# CUSTOMIZED_UN0O_BOARD.net
KiCad netlist of a schematic drawn in EAGLE
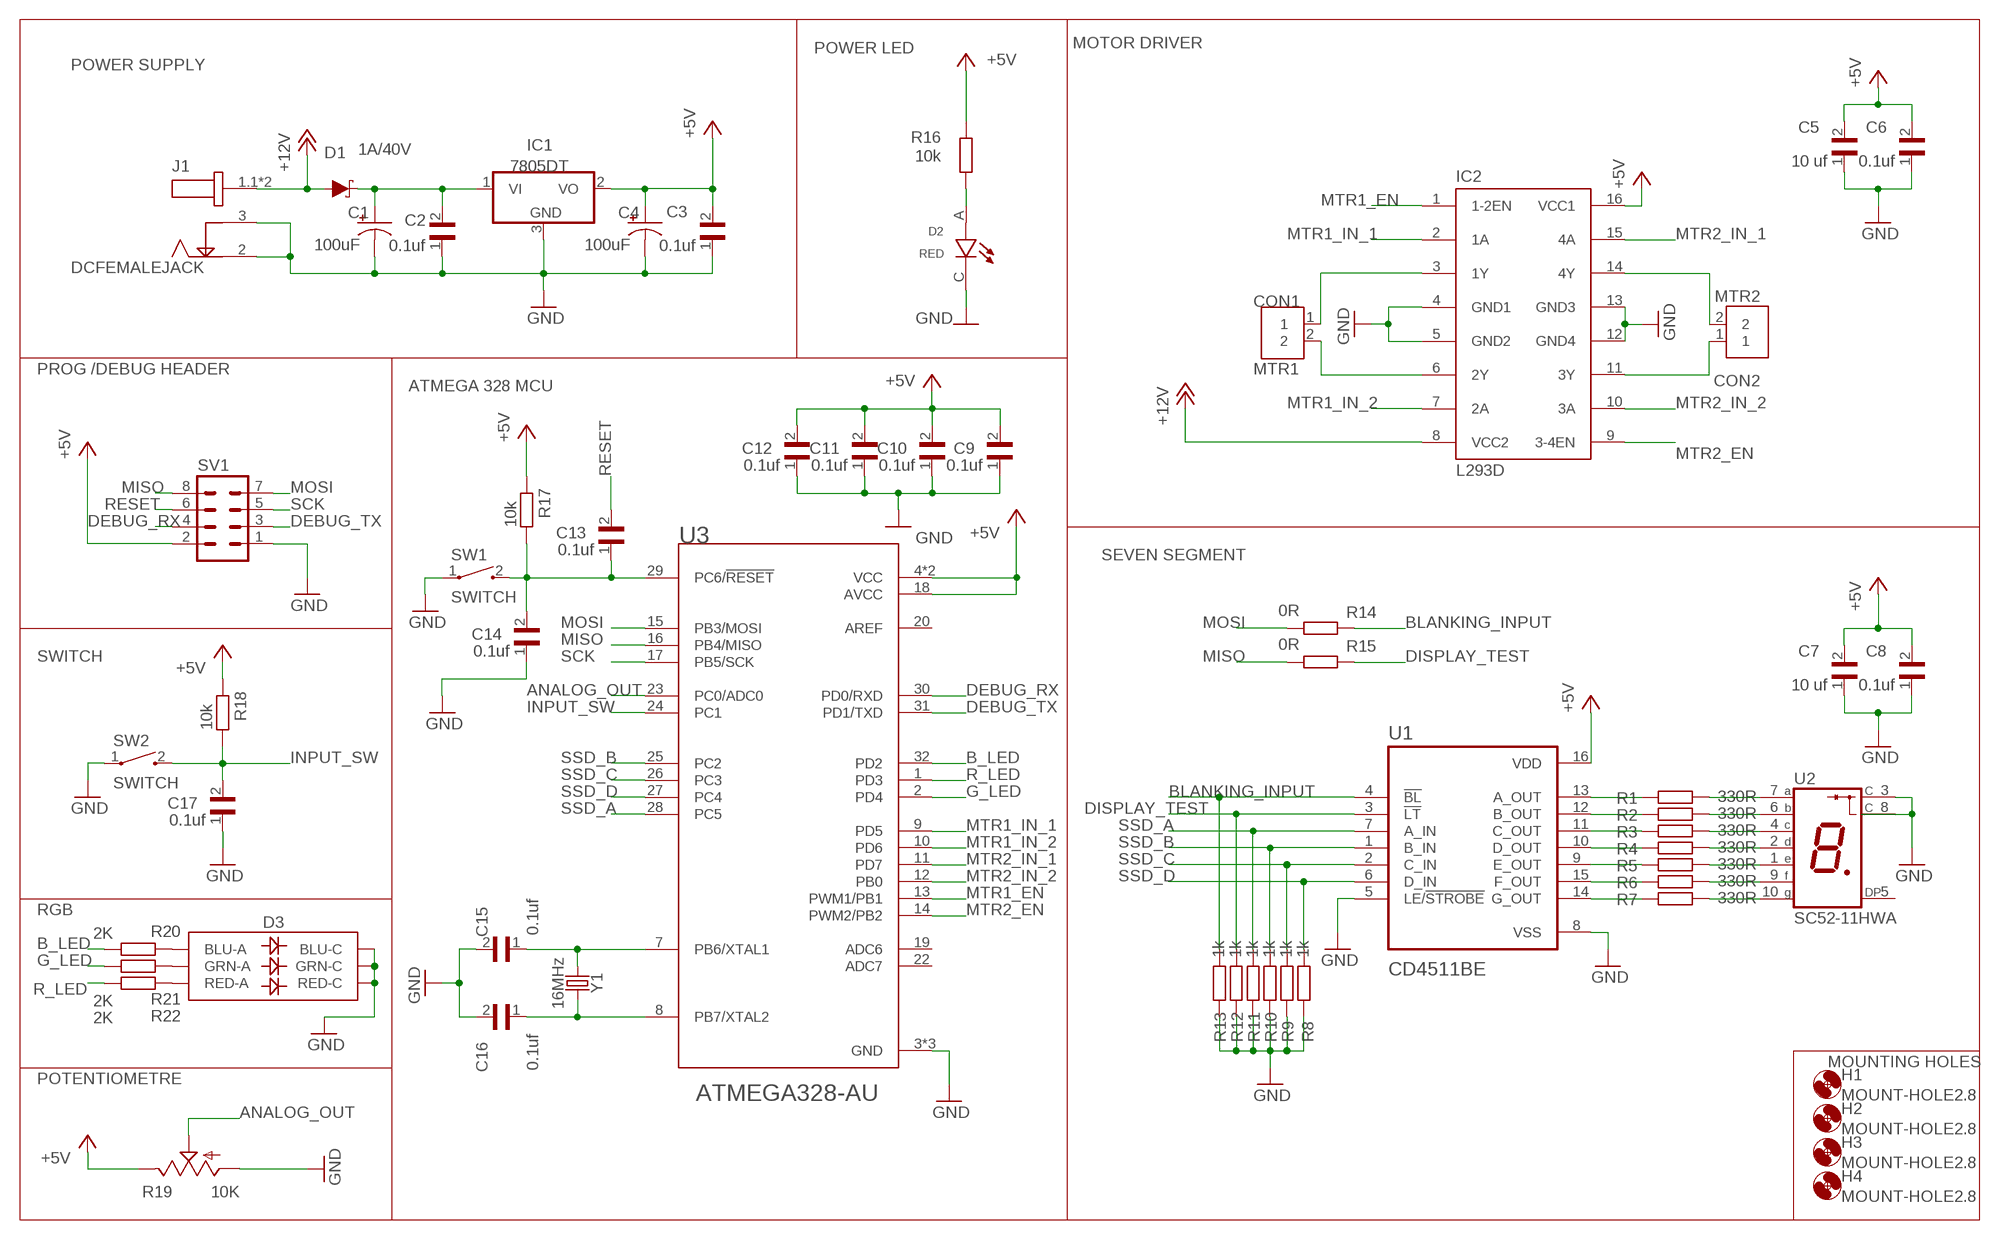
[diagram p0: schematic, sheet 1]

(export (version "E")
  (design (tool "Eeschema 10.0.6"))
  (components
    (comp (ref "C1")
      (value "100uF")
      (footprint "eagle-import:CPOL-RADIAL-2.5MM-6.5MM")
      (libsource (lib "eagle-import") (part "100UF-POLAR-RADIAL-2.5MM-25V-20%"))
    )
    (comp (ref "C2")
      (value "CAPACITOR")
      (footprint "eagle-import:C0603")
      (fields
        (field (name "MF") "TDK")
        (field (name "MP") "CGA3E2X7R1H104K080AA")
        (field (name "C2") "0.1uf")
        (field (name "NULL") "0.1uf")
      )
      (libsource (lib "eagle-import") (part "CAPACITOR"))
    )
    (comp (ref "C3")
      (value "CAPACITOR")
      (footprint "eagle-import:C0603")
      (fields
        (field (name "MF") "TDK")
        (field (name "MP") "CGA3E2X7R1H104K080AA")
        (field (name "NULL") "0.1uf")
      )
      (libsource (lib "eagle-import") (part "CAPACITOR"))
    )
    (comp (ref "C4")
      (value "100uF")
      (footprint "eagle-import:CPOL-RADIAL-2.5MM-6.5MM")
      (libsource (lib "eagle-import") (part "100UF-POLAR-RADIAL-2.5MM-25V-20%"))
    )
    (comp (ref "C5")
      (value "CAPACITOR")
      (footprint "eagle-import:C0603")
      (fields
        (field (name "MF") "TDK")
        (field (name "MP") "CGA3E2X7R1H104K080AA")
        (field (name "C3") "10 uf")
        (field (name "NO") "10")
        (field (name "NULL") "0.1uf")
      )
      (libsource (lib "eagle-import") (part "CAPACITOR"))
    )
    (comp (ref "C6")
      (value "CAPACITOR")
      (footprint "eagle-import:C0603")
      (fields
        (field (name "MF") "TDK")
        (field (name "MP") "CGA3E2X7R1H104K080AA")
        (field (name "NULL") "0.1uf")
      )
      (libsource (lib "eagle-import") (part "CAPACITOR"))
    )
    (comp (ref "C7")
      (value "CAPACITOR")
      (footprint "eagle-import:C0603")
      (fields
        (field (name "MF") "TDK")
        (field (name "MP") "CGA3E2X7R1H104K080AA")
        (field (name "C3") "10 uf")
        (field (name "NO") "10")
        (field (name "NULL") "0.1uf")
      )
      (libsource (lib "eagle-import") (part "CAPACITOR"))
    )
    (comp (ref "C8")
      (value "CAPACITOR")
      (footprint "eagle-import:C0603")
      (fields
        (field (name "MF") "TDK")
        (field (name "MP") "CGA3E2X7R1H104K080AA")
        (field (name "NULL") "0.1uf")
      )
      (libsource (lib "eagle-import") (part "CAPACITOR"))
    )
    (comp (ref "C9")
      (value "CAPACITOR")
      (footprint "eagle-import:C0603")
      (fields
        (field (name "MF") "TDK")
        (field (name "MP") "CGA3E2X7R1H104K080AA")
        (field (name "NULL") "0.1uf")
      )
      (libsource (lib "eagle-import") (part "CAPACITOR"))
    )
    (comp (ref "C10")
      (value "CAPACITOR")
      (footprint "eagle-import:C0603")
      (fields
        (field (name "MF") "TDK")
        (field (name "MP") "CGA3E2X7R1H104K080AA")
        (field (name "NULL") "0.1uf")
      )
      (libsource (lib "eagle-import") (part "CAPACITOR"))
    )
    (comp (ref "C11")
      (value "CAPACITOR")
      (footprint "eagle-import:C0603")
      (fields
        (field (name "MF") "TDK")
        (field (name "MP") "CGA3E2X7R1H104K080AA")
        (field (name "NULL") "0.1uf")
      )
      (libsource (lib "eagle-import") (part "CAPACITOR"))
    )
    (comp (ref "C12")
      (value "CAPACITOR")
      (footprint "eagle-import:C0603")
      (fields
        (field (name "MF") "TDK")
        (field (name "MP") "CGA3E2X7R1H104K080AA")
        (field (name "NULL") "0.1uf")
      )
      (libsource (lib "eagle-import") (part "CAPACITOR"))
    )
    (comp (ref "C13")
      (value "CAPACITOR")
      (footprint "eagle-import:C0603")
      (fields
        (field (name "MF") "TDK")
        (field (name "MP") "CGA3E2X7R1H104K080AA")
        (field (name "NULL") "0.1uf")
      )
      (libsource (lib "eagle-import") (part "CAPACITOR"))
    )
    (comp (ref "C14")
      (value "CAPACITOR")
      (footprint "eagle-import:C0603")
      (fields
        (field (name "MF") "TDK")
        (field (name "MP") "CGA3E2X7R1H104K080AA")
        (field (name "NULL") "0.1uf")
      )
      (libsource (lib "eagle-import") (part "CAPACITOR"))
    )
    (comp (ref "C15")
      (value "CAPACITOR")
      (footprint "eagle-import:C0603")
      (fields
        (field (name "MF") "TDK")
        (field (name "MP") "CGA3E2X7R1H104K080AA")
        (field (name "NULL") "0.1uf")
      )
      (libsource (lib "eagle-import") (part "CAPACITOR"))
    )
    (comp (ref "C16")
      (value "22pf")
      (footprint "eagle-import:C0603")
      (fields
        (field (name "MF") "TDK")
        (field (name "MP") "CGA3E2X7R1H104K080AA")
        (field (name "NULL") "0.1uf")
      )
      (libsource (lib "eagle-import") (part "CAPACITOR"))
    )
    (comp (ref "C17")
      (value "CAPACITOR")
      (footprint "eagle-import:C0603")
      (fields
        (field (name "MF") "TDK")
        (field (name "MP") "CGA3E2X7R1H104K080AA")
        (field (name "NULL") "0.1uf")
      )
      (libsource (lib "eagle-import") (part "CAPACITOR"))
    )
    (comp (ref "D1")
      (value "3A/40V/500mV")
      (footprint "eagle-import:SMA-DIODE")
      (fields (field (name "D1") "1A,40V") (field (name "NULL") "1A/40V"))
      (libsource (lib "eagle-import") (part "DIODE-SCHOTTKY-B340A"))
    )
    (comp (ref "D2")
      (value "RED")
      (footprint "eagle-import:LEDC1608X65N")
      (fields (field (name "MF") "Lite-On") (field (name "MP") "LTW-C191TLA"))
      (libsource (lib "eagle-import") (part "LTW-C191TLA"))
    )
    (comp (ref "D3")
      (value "LED-RGBNO_IC")
      (footprint "eagle-import:LED-TRICOLOR-5050")
      (libsource (lib "eagle-import") (part "LED-RGBNO_IC"))
    )
    (comp (ref "H1")
      (value "MOUNT-HOLE2.8")
      (footprint "eagle-import:2,8")
      (libsource (lib "eagle-import") (part "MOUNT-HOLE2.8"))
    )
    (comp (ref "H2")
      (value "MOUNT-HOLE2.8")
      (footprint "eagle-import:2,8")
      (libsource (lib "eagle-import") (part "MOUNT-HOLE2.8"))
    )
    (comp (ref "H3")
      (value "MOUNT-HOLE2.8")
      (footprint "eagle-import:2,8")
      (libsource (lib "eagle-import") (part "MOUNT-HOLE2.8"))
    )
    (comp (ref "H4")
      (value "MOUNT-HOLE2.8")
      (footprint "eagle-import:2,8")
      (libsource (lib "eagle-import") (part "MOUNT-HOLE2.8"))
    )
    (comp (ref "IC1")
      (value "7806DT")
      (footprint "eagle-import:TO252")
      (fields (field (name "K") "7805DT"))
      (libsource (lib "eagle-import") (part "78DT06"))
    )
    (comp (ref "IC2")
      (value "L293D")
      (footprint "eagle-import:DIL16")
      (libsource (lib "eagle-import") (part "L293D"))
    )
    (comp (ref "J1")
      (value "DCJ200-05-A-XX-X_REVA")
      (footprint "eagle-import:GCT_DCJ200-05-A-XX-X_REVA")
      (fields (field (name "MF") "Global Connector Technology") (field (name "MP") "DCJ200-05-A-K1-A"))
      (libsource (lib "eagle-import") (part "DCJ200-05-A-XX-X_REVA"))
    )
    (comp (ref "J2")
      (value "282836-2")
      (footprint "eagle-import:CONN_282836-2")
      (fields (field (name "MF") "TE Connectivity"))
      (libsource (lib "eagle-import") (part "282836-2"))
    )
    (comp (ref "J3")
      (value "282836-2")
      (footprint "eagle-import:CONN_282836-2")
      (fields (field (name "MF") "TE Connectivity"))
      (libsource (lib "eagle-import") (part "282836-2"))
    )
    (comp (ref "R1")
      (value "330R")
      (footprint "eagle-import:R0603")
      (fields (field (name "MF") "Yageo"))
      (libsource (lib "eagle-import") (part "RESISTOR"))
    )
    (comp (ref "R2")
      (value "330R")
      (footprint "eagle-import:R0603")
      (fields (field (name "MF") "Yageo"))
      (libsource (lib "eagle-import") (part "RESISTOR"))
    )
    (comp (ref "R3")
      (value "330R")
      (footprint "eagle-import:R0603")
      (fields (field (name "MF") "Yageo"))
      (libsource (lib "eagle-import") (part "RESISTOR"))
    )
    (comp (ref "R4")
      (value "330R")
      (footprint "eagle-import:R0603")
      (fields (field (name "MF") "Yageo"))
      (libsource (lib "eagle-import") (part "RESISTOR"))
    )
    (comp (ref "R5")
      (value "330R")
      (footprint "eagle-import:R0603")
      (fields (field (name "MF") "Yageo"))
      (libsource (lib "eagle-import") (part "RESISTOR"))
    )
    (comp (ref "R6")
      (value "330R")
      (footprint "eagle-import:R0603")
      (fields (field (name "MF") "Yageo"))
      (libsource (lib "eagle-import") (part "RESISTOR"))
    )
    (comp (ref "R7")
      (value "330R")
      (footprint "eagle-import:R0603")
      (fields (field (name "MF") "Yageo"))
      (libsource (lib "eagle-import") (part "RESISTOR"))
    )
    (comp (ref "R8")
      (value "1k")
      (footprint "eagle-import:R0603")
      (fields (field (name "MF") "Yageo"))
      (libsource (lib "eagle-import") (part "RESISTOR"))
    )
    (comp (ref "R9")
      (value "1k")
      (footprint "eagle-import:R0603")
      (fields (field (name "MF") "Yageo"))
      (libsource (lib "eagle-import") (part "RESISTOR"))
    )
    (comp (ref "R10")
      (value "1k")
      (footprint "eagle-import:R0603")
      (fields (field (name "MF") "Yageo"))
      (libsource (lib "eagle-import") (part "RESISTOR"))
    )
    (comp (ref "R11")
      (value "1k")
      (footprint "eagle-import:R0603")
      (fields (field (name "MF") "Yageo"))
      (libsource (lib "eagle-import") (part "RESISTOR"))
    )
    (comp (ref "R12")
      (value "1k")
      (footprint "eagle-import:R0603")
      (fields (field (name "MF") "Yageo"))
      (libsource (lib "eagle-import") (part "RESISTOR"))
    )
    (comp (ref "R13")
      (value "1k")
      (footprint "eagle-import:R0603")
      (fields (field (name "MF") "Yageo"))
      (libsource (lib "eagle-import") (part "RESISTOR"))
    )
    (comp (ref "R14")
      (value "0R")
      (footprint "eagle-import:R0603")
      (fields (field (name "MF") "Yageo"))
      (libsource (lib "eagle-import") (part "RESISTOR"))
    )
    (comp (ref "R15")
      (value "0R")
      (footprint "eagle-import:R0603")
      (fields (field (name "MF") "Yageo"))
      (libsource (lib "eagle-import") (part "RESISTOR"))
    )
    (comp (ref "R16")
      (value "10k")
      (footprint "eagle-import:R0603")
      (fields (field (name "MF") "Yageo"))
      (libsource (lib "eagle-import") (part "RESISTOR"))
    )
    (comp (ref "R17")
      (value "10k")
      (footprint "eagle-import:R0603")
      (fields (field (name "MF") "Yageo"))
      (libsource (lib "eagle-import") (part "RESISTOR"))
    )
    (comp (ref "R18")
      (value "10k")
      (footprint "eagle-import:R0603")
      (fields (field (name "MF") "Yageo"))
      (libsource (lib "eagle-import") (part "RESISTOR"))
    )
    (comp (ref "R19")
      (value "10K")
      (footprint "eagle-import:S64W")
      (libsource (lib "eagle-import") (part "TRIM_US-S64W"))
    )
    (comp (ref "R20")
      (value "2K")
      (footprint "eagle-import:R0603")
      (fields (field (name "MF") "Yageo"))
      (libsource (lib "eagle-import") (part "RESISTOR"))
    )
    (comp (ref "R21")
      (value "2K")
      (footprint "eagle-import:R0603")
      (fields (field (name "MF") "Yageo"))
      (libsource (lib "eagle-import") (part "RESISTOR"))
    )
    (comp (ref "R22")
      (value "2K")
      (footprint "eagle-import:R0603")
      (fields (field (name "MF") "Yageo"))
      (libsource (lib "eagle-import") (part "RESISTOR"))
    )
    (comp (ref "SV1")
      (value "MA04-2")
      (footprint "eagle-import:MA04-2")
      (libsource (lib "eagle-import") (part "MA04-2"))
    )
    (comp (ref "SW1")
      (value "SWITCH")
      (footprint "eagle-import:SW_1437566-3")
      (fields (field (name "COMMENT") "1437566-3") (field (name "MF") "TE Connectivity"))
      (libsource (lib "eagle-import") (part "1437566-3"))
    )
    (comp (ref "SW2")
      (value "SWITCH")
      (footprint "eagle-import:SW_1437566-3")
      (fields (field (name "COMMENT") "1437566-3") (field (name "MF") "TE Connectivity"))
      (libsource (lib "eagle-import") (part "1437566-3"))
    )
    (comp (ref "U1")
      (value "CD4511BE")
      (footprint "eagle-import:DIP794W45P254L1969H508Q16")
      (fields (field (name "MF") "Texas Instruments"))
      (libsource (lib "eagle-import") (part "CD4511BE"))
    )
    (comp (ref "U2")
      (value "SC52-11HWA")
      (footprint "eagle-import:LED_SC52-11HWA")
      (fields (field (name "MF") "Kingbright"))
      (libsource (lib "eagle-import") (part "SC52-11HWA"))
    )
    (comp (ref "U3")
      (value "ATMEGA328-AU")
      (footprint "eagle-import:QFP80P900X900X120-32N")
      (fields (field (name "MF") "Microchip"))
      (libsource (lib "eagle-import") (part "ATMEGA328-AU"))
    )
    (comp (ref "Y1")
      (value "16MHz")
      (footprint "eagle-import:HC49US")
      (libsource (lib "eagle-import") (part "CRYSTAL-16MHZPTH-HC49US"))
    )
  )
  (nets
    (net (code "1") (name "+5V") (class "Default")
      (node (ref "C10") (pin "2") (pinfunction "2_2") (pintype "passive"))
      (node (ref "C11") (pin "2") (pinfunction "2_2") (pintype "passive"))
      (node (ref "C12") (pin "2") (pinfunction "2_2") (pintype "passive"))
      (node (ref "C3") (pin "2") (pinfunction "2_2") (pintype "passive"))
      (node (ref "C4") (pin "1") (pinfunction "+_1") (pintype "passive"))
      (node (ref "C5") (pin "2") (pinfunction "2_2") (pintype "passive"))
      (node (ref "C6") (pin "2") (pinfunction "2_2") (pintype "passive"))
      (node (ref "C7") (pin "2") (pinfunction "2_2") (pintype "passive"))
      (node (ref "C8") (pin "2") (pinfunction "2_2") (pintype "passive"))
      (node (ref "C9") (pin "2") (pinfunction "2_2") (pintype "passive"))
      (node (ref "IC1") (pin "2") (pinfunction "VO_2") (pintype "passive"))
      (node (ref "IC2") (pin "16") (pinfunction "VCC1_16") (pintype "power_in"))
      (node (ref "R16") (pin "2") (pinfunction "2_2") (pintype "passive"))
      (node (ref "R17") (pin "2") (pinfunction "2_2") (pintype "passive"))
      (node (ref "R18") (pin "2") (pinfunction "2_2") (pintype "passive"))
      (node (ref "R19") (pin "E") (pinfunction "E_E") (pintype "passive"))
      (node (ref "SV1") (pin "2") (pinfunction "2_2") (pintype "passive"))
      (node (ref "U1") (pin "16") (pinfunction "VDD_16") (pintype "power_in"))
      (node (ref "U3") (pin "18") (pinfunction "AVCC_18") (pintype "power_in"))
      (node (ref "U3") (pin "4") (pinfunction "VCC_4") (pintype "power_in"))
      (node (ref "U3") (pin "6") (pinfunction "VCC_6") (pintype "power_in"))
    )
    (net (code "2") (name "+12V") (class "Default")
      (node (ref "D1") (pin "A") (pinfunction "A_A") (pintype "passive"))
      (node (ref "IC2") (pin "8") (pinfunction "VCC2_8") (pintype "power_in"))
      (node (ref "J1") (pin "1.1") (pinfunction "1_1.1") (pintype "passive"))
      (node (ref "J1") (pin "1.2") (pinfunction "1_1.2") (pintype "passive"))
    )
    (net (code "3") (name "ANALOG_OUT") (class "Default")
      (node (ref "R19") (pin "S") (pinfunction "S_S") (pintype "passive"))
      (node (ref "U3") (pin "23") (pinfunction "PC0/ADC0_23") (pintype "bidirectional"))
    )
    (net (code "4") (name "BLANKING_INPUT") (class "Default")
      (node (ref "R13") (pin "2") (pinfunction "2_2") (pintype "passive"))
      (node (ref "R14") (pin "2") (pinfunction "2_2") (pintype "passive"))
      (node (ref "U1") (pin "4") (pinfunction "~{BL}_4") (pintype "input"))
    )
    (net (code "5") (name "B_LED") (class "Default")
      (node (ref "R20") (pin "2") (pinfunction "2_2") (pintype "passive"))
      (node (ref "U3") (pin "32") (pinfunction "PD2_32") (pintype "bidirectional"))
    )
    (net (code "6") (name "DEBUG_RX") (class "Default")
      (node (ref "SV1") (pin "4") (pinfunction "4_4") (pintype "passive"))
      (node (ref "U3") (pin "30") (pinfunction "PD0/RXD_30") (pintype "bidirectional"))
    )
    (net (code "7") (name "DEBUG_TX") (class "Default")
      (node (ref "SV1") (pin "3") (pinfunction "3_3") (pintype "passive"))
      (node (ref "U3") (pin "31") (pinfunction "PD1/TXD_31") (pintype "bidirectional"))
    )
    (net (code "8") (name "DISPLAY_TEST") (class "Default")
      (node (ref "R12") (pin "2") (pinfunction "2_2") (pintype "passive"))
      (node (ref "R15") (pin "2") (pinfunction "2_2") (pintype "passive"))
      (node (ref "U1") (pin "3") (pinfunction "~{LT}_3") (pintype "input"))
    )
    (net (code "9") (name "GND") (class "Default")
      (node (ref "C1") (pin "2") (pinfunction "-_2") (pintype "passive"))
      (node (ref "C10") (pin "1") (pinfunction "1_1") (pintype "passive"))
      (node (ref "C11") (pin "1") (pinfunction "1_1") (pintype "passive"))
      (node (ref "C12") (pin "1") (pinfunction "1_1") (pintype "passive"))
      (node (ref "C14") (pin "1") (pinfunction "1_1") (pintype "passive"))
      (node (ref "C15") (pin "2") (pinfunction "2_2") (pintype "passive"))
      (node (ref "C16") (pin "2") (pinfunction "2_2") (pintype "passive"))
      (node (ref "C17") (pin "1") (pinfunction "1_1") (pintype "passive"))
      (node (ref "C2") (pin "1") (pinfunction "1_1") (pintype "passive"))
      (node (ref "C3") (pin "1") (pinfunction "1_1") (pintype "passive"))
      (node (ref "C4") (pin "2") (pinfunction "-_2") (pintype "passive"))
      (node (ref "C5") (pin "1") (pinfunction "1_1") (pintype "passive"))
      (node (ref "C6") (pin "1") (pinfunction "1_1") (pintype "passive"))
      (node (ref "C7") (pin "1") (pinfunction "1_1") (pintype "passive"))
      (node (ref "C8") (pin "1") (pinfunction "1_1") (pintype "passive"))
      (node (ref "C9") (pin "1") (pinfunction "1_1") (pintype "passive"))
      (node (ref "D2") (pin "C") (pinfunction "C_C") (pintype "passive"))
      (node (ref "D3") (pin "4") (pinfunction "BLU-C_4") (pintype "bidirectional"))
      (node (ref "D3") (pin "5") (pinfunction "RED-C_5") (pintype "bidirectional"))
      (node (ref "D3") (pin "6") (pinfunction "GRN-C_6") (pintype "bidirectional"))
      (node (ref "IC1") (pin "3") (pinfunction "GND_3") (pintype "passive"))
      (node (ref "IC2") (pin "12") (pinfunction "GND4_12") (pintype "power_in"))
      (node (ref "IC2") (pin "13") (pinfunction "GND3_13") (pintype "power_in"))
      (node (ref "IC2") (pin "4") (pinfunction "GND1_4") (pintype "power_in"))
      (node (ref "IC2") (pin "5") (pinfunction "GND2_5") (pintype "power_in"))
      (node (ref "J1") (pin "2") (pinfunction "2_2") (pintype "passive"))
      (node (ref "J1") (pin "3") (pinfunction "3_3") (pintype "passive"))
      (node (ref "R10") (pin "1") (pinfunction "1_1") (pintype "passive"))
      (node (ref "R11") (pin "1") (pinfunction "1_1") (pintype "passive"))
      (node (ref "R12") (pin "1") (pinfunction "1_1") (pintype "passive"))
      (node (ref "R13") (pin "1") (pinfunction "1_1") (pintype "passive"))
      (node (ref "R19") (pin "A") (pinfunction "A_A") (pintype "passive"))
      (node (ref "R8") (pin "1") (pinfunction "1_1") (pintype "passive"))
      (node (ref "R9") (pin "1") (pinfunction "1_1") (pintype "passive"))
      (node (ref "SV1") (pin "1") (pinfunction "1_1") (pintype "passive"))
      (node (ref "SW1") (pin "1") (pinfunction "1_1") (pintype "passive"))
      (node (ref "SW2") (pin "1") (pinfunction "1_1") (pintype "passive"))
      (node (ref "U1") (pin "5") (pinfunction "LE/~{STROBE}_5") (pintype "input"))
      (node (ref "U1") (pin "8") (pinfunction "VSS_8") (pintype "power_in"))
      (node (ref "U2") (pin "3") (pinfunction "C_3") (pintype "passive"))
      (node (ref "U2") (pin "8") (pinfunction "C_8") (pintype "passive"))
      (node (ref "U3") (pin "21") (pinfunction "GND_21") (pintype "power_in"))
      (node (ref "U3") (pin "3") (pinfunction "GND_3") (pintype "power_in"))
      (node (ref "U3") (pin "5") (pinfunction "GND_5") (pintype "power_in"))
    )
    (net (code "10") (name "G_LED") (class "Default")
      (node (ref "R21") (pin "2") (pinfunction "2_2") (pintype "passive"))
      (node (ref "U3") (pin "2") (pinfunction "PD4_2") (pintype "bidirectional"))
    )
    (net (code "11") (name "INPUT_SW") (class "Default")
      (node (ref "C17") (pin "2") (pinfunction "2_2") (pintype "passive"))
      (node (ref "R18") (pin "1") (pinfunction "1_1") (pintype "passive"))
      (node (ref "SW2") (pin "2") (pinfunction "2_2") (pintype "passive"))
      (node (ref "U3") (pin "24") (pinfunction "PC1_24") (pintype "bidirectional"))
    )
    (net (code "12") (name "MISO") (class "Default")
      (node (ref "R15") (pin "1") (pinfunction "1_1") (pintype "passive"))
      (node (ref "SV1") (pin "8") (pinfunction "8_8") (pintype "passive"))
      (node (ref "U3") (pin "16") (pinfunction "PB4/MISO_16") (pintype "bidirectional"))
    )
    (net (code "13") (name "MOSI") (class "Default")
      (node (ref "R14") (pin "1") (pinfunction "1_1") (pintype "passive"))
      (node (ref "SV1") (pin "7") (pinfunction "7_7") (pintype "passive"))
      (node (ref "U3") (pin "15") (pinfunction "PB3/MOSI_15") (pintype "bidirectional"))
    )
    (net (code "14") (name "MTR1_EN") (class "Default")
      (node (ref "IC2") (pin "1") (pinfunction "1-2EN_1") (pintype "input"))
      (node (ref "U3") (pin "13") (pinfunction "PWM1/PB1_13") (pintype "bidirectional"))
    )
    (net (code "15") (name "MTR1_IN_1") (class "Default")
      (node (ref "IC2") (pin "2") (pinfunction "1A_2") (pintype "input"))
      (node (ref "U3") (pin "9") (pinfunction "PD5_9") (pintype "bidirectional"))
    )
    (net (code "16") (name "MTR1_IN_2") (class "Default")
      (node (ref "IC2") (pin "7") (pinfunction "2A_7") (pintype "input"))
      (node (ref "U3") (pin "10") (pinfunction "PD6_10") (pintype "bidirectional"))
    )
    (net (code "17") (name "MTR2_EN") (class "Default")
      (node (ref "IC2") (pin "9") (pinfunction "3-4EN_9") (pintype "input"))
      (node (ref "U3") (pin "14") (pinfunction "PWM2/PB2_14") (pintype "bidirectional"))
    )
    (net (code "18") (name "MTR2_IN_1") (class "Default")
      (node (ref "IC2") (pin "15") (pinfunction "4A_15") (pintype "input"))
      (node (ref "U3") (pin "11") (pinfunction "PD7_11") (pintype "bidirectional"))
    )
    (net (code "19") (name "MTR2_IN_2") (class "Default")
      (node (ref "IC2") (pin "10") (pinfunction "3A_10") (pintype "input"))
      (node (ref "U3") (pin "12") (pinfunction "PB0_12") (pintype "bidirectional"))
    )
    (net (code "20") (name "Net-(C1-+)") (class "Default")
      (node (ref "C1") (pin "1") (pinfunction "+_1") (pintype "passive"))
      (node (ref "C2") (pin "2") (pinfunction "2_2") (pintype "passive"))
      (node (ref "D1") (pin "C") (pinfunction "C_C") (pintype "passive"))
      (node (ref "IC1") (pin "1") (pinfunction "VI_1") (pintype "input"))
    )
    (net (code "21") (name "Net-(D2-PadA)") (class "Default")
      (node (ref "D2") (pin "A") (pinfunction "A_A") (pintype "passive"))
      (node (ref "R16") (pin "1") (pinfunction "1_1") (pintype "passive"))
    )
    (net (code "22") (name "Net-(D3-BLU-A)") (class "Default")
      (node (ref "D3") (pin "3") (pinfunction "BLU-A_3") (pintype "bidirectional"))
      (node (ref "R20") (pin "1") (pinfunction "1_1") (pintype "passive"))
    )
    (net (code "23") (name "Net-(D3-GRN-A)") (class "Default")
      (node (ref "D3") (pin "1") (pinfunction "GRN-A_1") (pintype "bidirectional"))
      (node (ref "R21") (pin "1") (pinfunction "1_1") (pintype "passive"))
    )
    (net (code "24") (name "Net-(D3-RED-A)") (class "Default")
      (node (ref "D3") (pin "2") (pinfunction "RED-A_2") (pintype "bidirectional"))
      (node (ref "R22") (pin "1") (pinfunction "1_1") (pintype "passive"))
    )
    (net (code "25") (name "Net-(IC2-1Y)") (class "Default")
      (node (ref "IC2") (pin "3") (pinfunction "1Y_3") (pintype "output"))
      (node (ref "J2") (pin "1") (pinfunction "1_1") (pintype "passive"))
    )
    (net (code "26") (name "Net-(IC2-2Y)") (class "Default")
      (node (ref "IC2") (pin "6") (pinfunction "2Y_6") (pintype "output"))
      (node (ref "J2") (pin "2") (pinfunction "2_2") (pintype "passive"))
    )
    (net (code "27") (name "Net-(IC2-3Y)") (class "Default")
      (node (ref "IC2") (pin "11") (pinfunction "3Y_11") (pintype "output"))
      (node (ref "J3") (pin "1") (pinfunction "1_1") (pintype "passive"))
    )
    (net (code "28") (name "Net-(IC2-4Y)") (class "Default")
      (node (ref "IC2") (pin "14") (pinfunction "4Y_14") (pintype "output"))
      (node (ref "J3") (pin "2") (pinfunction "2_2") (pintype "passive"))
    )
    (net (code "29") (name "Net-(R3-Pad2)") (class "Default")
      (node (ref "R3") (pin "2") (pinfunction "2_2") (pintype "passive"))
      (node (ref "U2") (pin "4") (pinfunction "C_4") (pintype "passive"))
    )
    (net (code "30") (name "Net-(U1-A_OUT)") (class "Default")
      (node (ref "R1") (pin "1") (pinfunction "1_1") (pintype "passive"))
      (node (ref "U1") (pin "13") (pinfunction "A_OUT_13") (pintype "output"))
    )
    (net (code "31") (name "Net-(U1-B_OUT)") (class "Default")
      (node (ref "R2") (pin "1") (pinfunction "1_1") (pintype "passive"))
      (node (ref "U1") (pin "12") (pinfunction "B_OUT_12") (pintype "output"))
    )
    (net (code "32") (name "Net-(U1-C_OUT)") (class "Default")
      (node (ref "R3") (pin "1") (pinfunction "1_1") (pintype "passive"))
      (node (ref "U1") (pin "11") (pinfunction "C_OUT_11") (pintype "output"))
    )
    (net (code "33") (name "Net-(U1-D_OUT)") (class "Default")
      (node (ref "R4") (pin "1") (pinfunction "1_1") (pintype "passive"))
      (node (ref "U1") (pin "10") (pinfunction "D_OUT_10") (pintype "output"))
    )
    (net (code "34") (name "Net-(U1-E_OUT)") (class "Default")
      (node (ref "R5") (pin "1") (pinfunction "1_1") (pintype "passive"))
      (node (ref "U1") (pin "9") (pinfunction "E_OUT_9") (pintype "output"))
    )
    (net (code "35") (name "Net-(U1-F_OUT)") (class "Default")
      (node (ref "R6") (pin "1") (pinfunction "1_1") (pintype "passive"))
      (node (ref "U1") (pin "15") (pinfunction "F_OUT_15") (pintype "output"))
    )
    (net (code "36") (name "Net-(U1-G_OUT)") (class "Default")
      (node (ref "R7") (pin "1") (pinfunction "1_1") (pintype "passive"))
      (node (ref "U1") (pin "14") (pinfunction "G_OUT_14") (pintype "output"))
    )
    (net (code "37") (name "Net-(U2-A)") (class "Default")
      (node (ref "R1") (pin "2") (pinfunction "2_2") (pintype "passive"))
      (node (ref "U2") (pin "7") (pinfunction "A_7") (pintype "passive"))
    )
    (net (code "38") (name "Net-(U2-B)") (class "Default")
      (node (ref "R2") (pin "2") (pinfunction "2_2") (pintype "passive"))
      (node (ref "U2") (pin "6") (pinfunction "B_6") (pintype "passive"))
    )
    (net (code "39") (name "Net-(U2-D)") (class "Default")
      (node (ref "R4") (pin "2") (pinfunction "2_2") (pintype "passive"))
      (node (ref "U2") (pin "2") (pinfunction "D_2") (pintype "passive"))
    )
    (net (code "40") (name "Net-(U2-E)") (class "Default")
      (node (ref "R5") (pin "2") (pinfunction "2_2") (pintype "passive"))
      (node (ref "U2") (pin "1") (pinfunction "E_1") (pintype "passive"))
    )
    (net (code "41") (name "Net-(U2-F)") (class "Default")
      (node (ref "R6") (pin "2") (pinfunction "2_2") (pintype "passive"))
      (node (ref "U2") (pin "9") (pinfunction "F_9") (pintype "passive"))
    )
    (net (code "42") (name "Net-(U2-G)") (class "Default")
      (node (ref "R7") (pin "2") (pinfunction "2_2") (pintype "passive"))
      (node (ref "U2") (pin "10") (pinfunction "G_10") (pintype "passive"))
    )
    (net (code "43") (name "Net-(U3-PB6{slash}XTAL1)") (class "Default")
      (node (ref "C15") (pin "1") (pinfunction "1_1") (pintype "passive"))
      (node (ref "U3") (pin "7") (pinfunction "PB6/XTAL1_7") (pintype "bidirectional"))
      (node (ref "Y1") (pin "1") (pinfunction "1_1") (pintype "passive"))
    )
    (net (code "44") (name "Net-(U3-PB7{slash}XTAL2)") (class "Default")
      (node (ref "C16") (pin "1") (pinfunction "1_1") (pintype "passive"))
      (node (ref "U3") (pin "8") (pinfunction "PB7/XTAL2_8") (pintype "bidirectional"))
      (node (ref "Y1") (pin "2") (pinfunction "2_2") (pintype "passive"))
    )
    (net (code "45") (name "Net-(U3-PC6{slash}~{RESET})") (class "Default")
      (node (ref "C13") (pin "1") (pinfunction "1_1") (pintype "passive"))
      (node (ref "C14") (pin "2") (pinfunction "2_2") (pintype "passive"))
      (node (ref "R17") (pin "1") (pinfunction "1_1") (pintype "passive"))
      (node (ref "SW1") (pin "2") (pinfunction "2_2") (pintype "passive"))
      (node (ref "U3") (pin "29") (pinfunction "PC6/~{RESET}_29") (pintype "bidirectional"))
    )
    (net (code "46") (name "RESET") (class "Default")
      (node (ref "C13") (pin "2") (pinfunction "2_2") (pintype "passive"))
      (node (ref "SV1") (pin "6") (pinfunction "6_6") (pintype "passive"))
    )
    (net (code "47") (name "R_LED") (class "Default")
      (node (ref "R22") (pin "2") (pinfunction "2_2") (pintype "passive"))
      (node (ref "U3") (pin "1") (pinfunction "PD3_1") (pintype "bidirectional"))
    )
    (net (code "48") (name "SCK") (class "Default")
      (node (ref "SV1") (pin "5") (pinfunction "5_5") (pintype "passive"))
      (node (ref "U3") (pin "17") (pinfunction "PB5/SCK_17") (pintype "bidirectional"))
    )
    (net (code "49") (name "SSD_A") (class "Default")
      (node (ref "R11") (pin "2") (pinfunction "2_2") (pintype "passive"))
      (node (ref "U1") (pin "7") (pinfunction "A_IN_7") (pintype "input"))
      (node (ref "U3") (pin "28") (pinfunction "PC5_28") (pintype "bidirectional"))
    )
    (net (code "50") (name "SSD_B") (class "Default")
      (node (ref "R10") (pin "2") (pinfunction "2_2") (pintype "passive"))
      (node (ref "U1") (pin "1") (pinfunction "B_IN_1") (pintype "input"))
      (node (ref "U3") (pin "25") (pinfunction "PC2_25") (pintype "bidirectional"))
    )
    (net (code "51") (name "SSD_C") (class "Default")
      (node (ref "R9") (pin "2") (pinfunction "2_2") (pintype "passive"))
      (node (ref "U1") (pin "2") (pinfunction "C_IN_2") (pintype "input"))
      (node (ref "U3") (pin "26") (pinfunction "PC3_26") (pintype "bidirectional"))
    )
    (net (code "52") (name "SSD_D") (class "Default")
      (node (ref "R8") (pin "2") (pinfunction "2_2") (pintype "passive"))
      (node (ref "U1") (pin "6") (pinfunction "D_IN_6") (pintype "input"))
      (node (ref "U3") (pin "27") (pinfunction "PC4_27") (pintype "bidirectional"))
    )
    (net (code "53") (name "unconnected-(U2-DP-Pad5)") (class "Default")
      (node (ref "U2") (pin "5") (pinfunction "DP_5") (pintype "passive"))
    )
    (net (code "54") (name "unconnected-(U3-ADC6-Pad19)") (class "Default")
      (node (ref "U3") (pin "19") (pinfunction "ADC6_19") (pintype "bidirectional"))
    )
    (net (code "55") (name "unconnected-(U3-ADC7-Pad22)") (class "Default")
      (node (ref "U3") (pin "22") (pinfunction "ADC7_22") (pintype "bidirectional"))
    )
    (net (code "56") (name "unconnected-(U3-AREF-Pad20)") (class "Default")
      (node (ref "U3") (pin "20") (pinfunction "AREF_20") (pintype "input"))
    )
  )
)
